# Low_Voltage_Regulator-pass_pnp.net
KiCad netlist of a schematic drawn in EAGLE
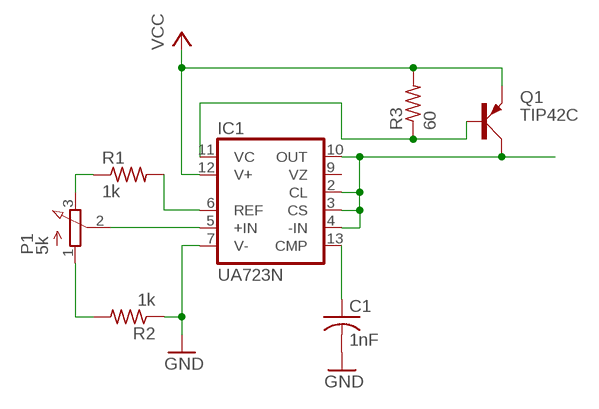
[diagram p0: schematic, sheet 1]

(export (version "E")
  (design (tool "Eeschema 10.0.6"))
  (components
    (comp (ref "C1")
      (value "1nF")
      (footprint "eagle-import:C050-025X075")
      (libsource (lib "eagle-import") (part "C-US050-025X075"))
    )
    (comp (ref "IC1")
      (value "UA723N")
      (footprint "eagle-import:DIL14")
      (libsource (lib "eagle-import") (part "723NUA"))
    )
    (comp (ref "P1")
      (value "5k")
      (footprint "eagle-import:3RP_1610N")
      (libsource (lib "eagle-import") (part "3RP/1610N"))
    )
    (comp (ref "Q1")
      (value "TIP42C")
      (footprint "eagle-import:TO220AV")
      (libsource (lib "eagle-import") (part "TIP42C"))
    )
    (comp (ref "R1")
      (value "1k")
      (footprint "eagle-import:0207_10")
      (libsource (lib "eagle-import") (part "R-US_0207/10"))
    )
    (comp (ref "R2")
      (value "1k")
      (footprint "eagle-import:0207_10")
      (libsource (lib "eagle-import") (part "R-US_0207/10"))
    )
    (comp (ref "R3")
      (value "60")
      (footprint "eagle-import:0207_10")
      (libsource (lib "eagle-import") (part "R-US_0207/10"))
    )
  )
  (nets
    (net (code "1") (name "GND") (class "Default")
      (node (ref "C1") (pin "2") (pinfunction "2_2") (pintype "passive"))
      (node (ref "IC1") (pin "7") (pinfunction "V-_7") (pintype "input"))
      (node (ref "R2") (pin "1") (pinfunction "1_1") (pintype "passive"))
    )
    (net (code "2") (name "Net-(IC1-+IN)") (class "Default")
      (node (ref "IC1") (pin "5") (pinfunction "+IN_5") (pintype "input"))
      (node (ref "P1") (pin "2") (pinfunction "S_2") (pintype "passive"))
    )
    (net (code "3") (name "Net-(IC1--IN)") (class "Default")
      (node (ref "IC1") (pin "10") (pinfunction "OUT_10") (pintype "output"))
      (node (ref "IC1") (pin "2") (pinfunction "CL_2") (pintype "input"))
      (node (ref "IC1") (pin "3") (pinfunction "CS_3") (pintype "input"))
      (node (ref "IC1") (pin "4") (pinfunction "-IN_4") (pintype "input"))
      (node (ref "Q1") (pin "C") (pinfunction "C_C") (pintype "passive"))
    )
    (net (code "4") (name "Net-(IC1-CMP)") (class "Default")
      (node (ref "C1") (pin "1") (pinfunction "1_1") (pintype "passive"))
      (node (ref "IC1") (pin "13") (pinfunction "CMP_13") (pintype "passive"))
    )
    (net (code "5") (name "Net-(IC1-REF)") (class "Default")
      (node (ref "IC1") (pin "6") (pinfunction "REF_6") (pintype "output"))
      (node (ref "R1") (pin "2") (pinfunction "2_2") (pintype "passive"))
    )
    (net (code "6") (name "Net-(IC1-VC)") (class "Default")
      (node (ref "IC1") (pin "11") (pinfunction "VC_11") (pintype "input"))
      (node (ref "Q1") (pin "B") (pinfunction "B_B") (pintype "passive"))
      (node (ref "R3") (pin "1") (pinfunction "1_1") (pintype "passive"))
    )
    (net (code "7") (name "Net-(P1-A)") (class "Default")
      (node (ref "P1") (pin "1") (pinfunction "A_1") (pintype "passive"))
      (node (ref "R2") (pin "2") (pinfunction "2_2") (pintype "passive"))
    )
    (net (code "8") (name "Net-(P1-E)") (class "Default")
      (node (ref "P1") (pin "3") (pinfunction "E_3") (pintype "passive"))
      (node (ref "R1") (pin "1") (pinfunction "1_1") (pintype "passive"))
    )
    (net (code "9") (name "VCC") (class "Default")
      (node (ref "IC1") (pin "12") (pinfunction "V+_12") (pintype "input"))
      (node (ref "Q1") (pin "E") (pinfunction "E_E") (pintype "passive"))
      (node (ref "R3") (pin "2") (pinfunction "2_2") (pintype "passive"))
    )
    (net (code "10") (name "unconnected-(IC1-VZ-Pad9)") (class "Default")
      (node (ref "IC1") (pin "9") (pinfunction "VZ_9") (pintype "output"))
    )
  )
)
